# Sheet2.net
KiCad netlist of a schematic drawn in Altium Designer
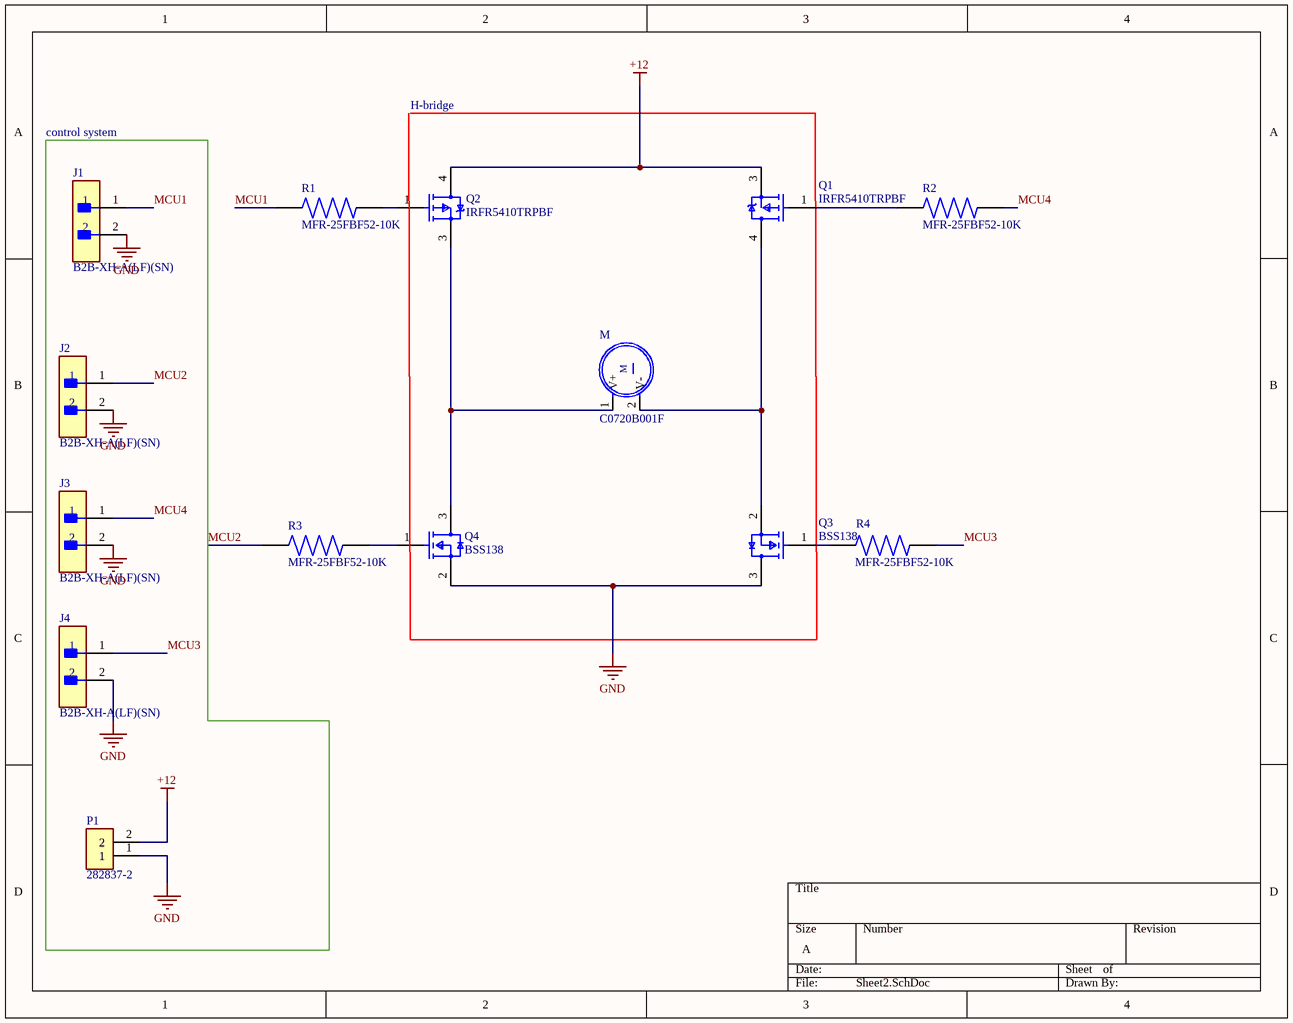
[diagram p0: Sheet2.SchDoc]

(export (version "E")
  (design (tool "Eeschema 10.0.6"))
  (components
    (comp (ref "J1")
      (value "B2B-XH-A(LF)(SN)")
      (footprint "FP-B2B-XH-A_LF_SN-MFG")
      (description "CONN HEADER VERT 2POS 2.5MM")
      (libsource (lib "Altium Content Vault") (part "3bc925449376181038e59eaffc5286c"))
    )
    (comp (ref "J2")
      (value "B2B-XH-A(LF)(SN)")
      (footprint "FP-B2B-XH-A_LF_SN-MFG")
      (description "CONN HEADER VERT 2POS 2.5MM")
      (libsource (lib "Altium Content Vault") (part "3bc925449376181038e59eaffc5286c"))
    )
    (comp (ref "J3")
      (value "B2B-XH-A(LF)(SN)")
      (footprint "FP-B2B-XH-A_LF_SN-MFG")
      (description "CONN HEADER VERT 2POS 2.5MM")
      (libsource (lib "Altium Content Vault") (part "3bc925449376181038e59eaffc5286c"))
    )
    (comp (ref "J4")
      (value "B2B-XH-A(LF)(SN)")
      (footprint "FP-B2B-XH-A_LF_SN-MFG")
      (description "CONN HEADER VERT 2POS 2.5MM")
      (libsource (lib "Altium Content Vault") (part "3bc925449376181038e59eaffc5286c"))
    )
    (comp (ref "M")
      (value "C0720B001F")
      (footprint "XDCR_C0720B001F")
      (description "DC Motor Vibration, ERM 10000 RPM 3VDC")
      (fields (field (name "MF") "Jinlong Machinery"))
      (libsource (lib "C0720B001F") (part "C0720B001F"))
    )
    (comp (ref "P1")
      (value "282837-2")
      (footprint "TE_282837-2")
      (fields (field (name "MF") "TE Connectivity"))
      (libsource (lib "282837-2") (part "282837-2"))
    )
    (comp (ref "Q1")
      (value "IRFR5410TRPBF")
      (footprint "FP-PG-TO252-3-MFG")
      (description "MOSFET P-CH 100V 13A DPAK")
      (fields
        (field (name "MANUFACTURER") "Infineon")
        (field (name "OCTOPART") "https://octopart.com/irfr5410trpbf-infineon-65874169")
      )
      (libsource (lib "Altium Content Vault") (part "84bd51c0c313388725e75e773aba525"))
    )
    (comp (ref "Q2")
      (value "IRFR5410TRPBF")
      (footprint "FP-PG-TO252-3-MFG")
      (description "MOSFET P-CH 100V 13A DPAK")
      (fields
        (field (name "MANUFACTURER") "Infineon")
        (field (name "OCTOPART") "https://octopart.com/irfr5410trpbf-infineon-65874169")
      )
      (libsource (lib "Altium Content Vault") (part "84bd51c0c313388725e75e773aba525"))
    )
    (comp (ref "Q3")
      (value "BSS138")
      (footprint "FP-318-08-IPC_B")
      (description "MOSFET N-CH 50V 220MA SOT-23")
      (libsource (lib "Altium Content Vault") (part "3b9c635fedb024a5347a57b145af9cc"))
    )
    (comp (ref "Q4")
      (value "BSS138")
      (footprint "FP-318-08-IPC_B")
      (description "MOSFET N-CH 50V 220MA SOT-23")
      (libsource (lib "Altium Content Vault") (part "3b9c635fedb024a5347a57b145af9cc"))
    )
    (comp (ref "R1")
      (value "MFR-25FBF52-10K")
      (footprint "RESAD1100W55L680D260")
      (description "10.2 kOhms Â±1% 0.25W, 1/4W Through Hole Resistor Axial - Metal Film")
      (fields (field (name "MF") "Yageo"))
      (libsource (lib "MFR-25FBF52-10K") (part "MFR-25FBF52-10K"))
    )
    (comp (ref "R2")
      (value "MFR-25FBF52-10K")
      (footprint "RESAD1100W55L680D260")
      (description "10.2 kOhms Â±1% 0.25W, 1/4W Through Hole Resistor Axial - Metal Film")
      (fields (field (name "MF") "Yageo"))
      (libsource (lib "MFR-25FBF52-10K") (part "MFR-25FBF52-10K"))
    )
    (comp (ref "R3")
      (value "MFR-25FBF52-10K")
      (footprint "RESAD1100W55L680D260")
      (description "10.2 kOhms Â±1% 0.25W, 1/4W Through Hole Resistor Axial - Metal Film")
      (fields (field (name "MF") "Yageo"))
      (libsource (lib "MFR-25FBF52-10K") (part "MFR-25FBF52-10K"))
    )
    (comp (ref "R4")
      (value "MFR-25FBF52-10K")
      (footprint "RESAD1100W55L680D260")
      (description "10.2 kOhms Â±1% 0.25W, 1/4W Through Hole Resistor Axial - Metal Film")
      (fields (field (name "MF") "Yageo"))
      (libsource (lib "MFR-25FBF52-10K") (part "MFR-25FBF52-10K"))
    )
  )
  (nets
    (net (code "1") (name "+12") (class "Default")
      (node (ref "P1") (pin "2") (pinfunction "2_2") (pintype "passive"))
      (node (ref "Q1") (pin "3") (pinfunction "S_3") (pintype "passive"))
      (node (ref "Q2") (pin "4") (pinfunction "D_4") (pintype "passive"))
    )
    (net (code "2") (name "/MCU1") (class "Default")
      (node (ref "J1") (pin "1") (pinfunction "1_1") (pintype "passive"))
      (node (ref "R1") (pin "1") (pinfunction "1_1") (pintype "passive"))
    )
    (net (code "3") (name "/MCU2") (class "Default")
      (node (ref "J2") (pin "1") (pinfunction "1_1") (pintype "passive"))
      (node (ref "R3") (pin "1") (pinfunction "1_1") (pintype "passive"))
    )
    (net (code "4") (name "/MCU3") (class "Default")
      (node (ref "J4") (pin "1") (pinfunction "1_1") (pintype "passive"))
      (node (ref "R4") (pin "2") (pinfunction "2_2") (pintype "passive"))
    )
    (net (code "5") (name "/MCU4") (class "Default")
      (node (ref "J3") (pin "1") (pinfunction "1_1") (pintype "passive"))
      (node (ref "R2") (pin "2") (pinfunction "2_2") (pintype "passive"))
    )
    (net (code "6") (name "GND") (class "Default")
      (node (ref "J1") (pin "2") (pinfunction "2_2") (pintype "passive"))
      (node (ref "J2") (pin "2") (pinfunction "2_2") (pintype "passive"))
      (node (ref "J3") (pin "2") (pinfunction "2_2") (pintype "passive"))
      (node (ref "J4") (pin "2") (pinfunction "2_2") (pintype "passive"))
      (node (ref "P1") (pin "1") (pinfunction "1_1") (pintype "passive"))
      (node (ref "Q3") (pin "3") (pinfunction "D_3") (pintype "passive"))
      (node (ref "Q4") (pin "2") (pinfunction "S_2") (pintype "passive"))
    )
    (net (code "7") (name "Net-(M-V+)") (class "Default")
      (node (ref "M") (pin "1") (pinfunction "V+_1") (pintype "power_in"))
      (node (ref "Q2") (pin "3") (pinfunction "S_3") (pintype "passive"))
      (node (ref "Q4") (pin "3") (pinfunction "D_3") (pintype "passive"))
    )
    (net (code "8") (name "Net-(M-V-)") (class "Default")
      (node (ref "M") (pin "2") (pinfunction "V-_2") (pintype "power_in"))
      (node (ref "Q1") (pin "4") (pinfunction "D_4") (pintype "passive"))
      (node (ref "Q3") (pin "2") (pinfunction "S_2") (pintype "passive"))
    )
    (net (code "9") (name "Net-(Q1-G)") (class "Default")
      (node (ref "Q1") (pin "1") (pinfunction "G_1") (pintype "passive"))
      (node (ref "R2") (pin "1") (pinfunction "1_1") (pintype "passive"))
    )
    (net (code "10") (name "Net-(Q2-G)") (class "Default")
      (node (ref "Q2") (pin "1") (pinfunction "G_1") (pintype "passive"))
      (node (ref "R1") (pin "2") (pinfunction "2_2") (pintype "passive"))
    )
    (net (code "11") (name "Net-(Q3-G)") (class "Default")
      (node (ref "Q3") (pin "1") (pinfunction "G_1") (pintype "passive"))
      (node (ref "R4") (pin "1") (pinfunction "1_1") (pintype "passive"))
    )
    (net (code "12") (name "Net-(Q4-G)") (class "Default")
      (node (ref "Q4") (pin "1") (pinfunction "G_1") (pintype "passive"))
      (node (ref "R3") (pin "2") (pinfunction "2_2") (pintype "passive"))
    )
  )
)
